# Power.net
KiCad netlist of a schematic drawn in Altium Designer
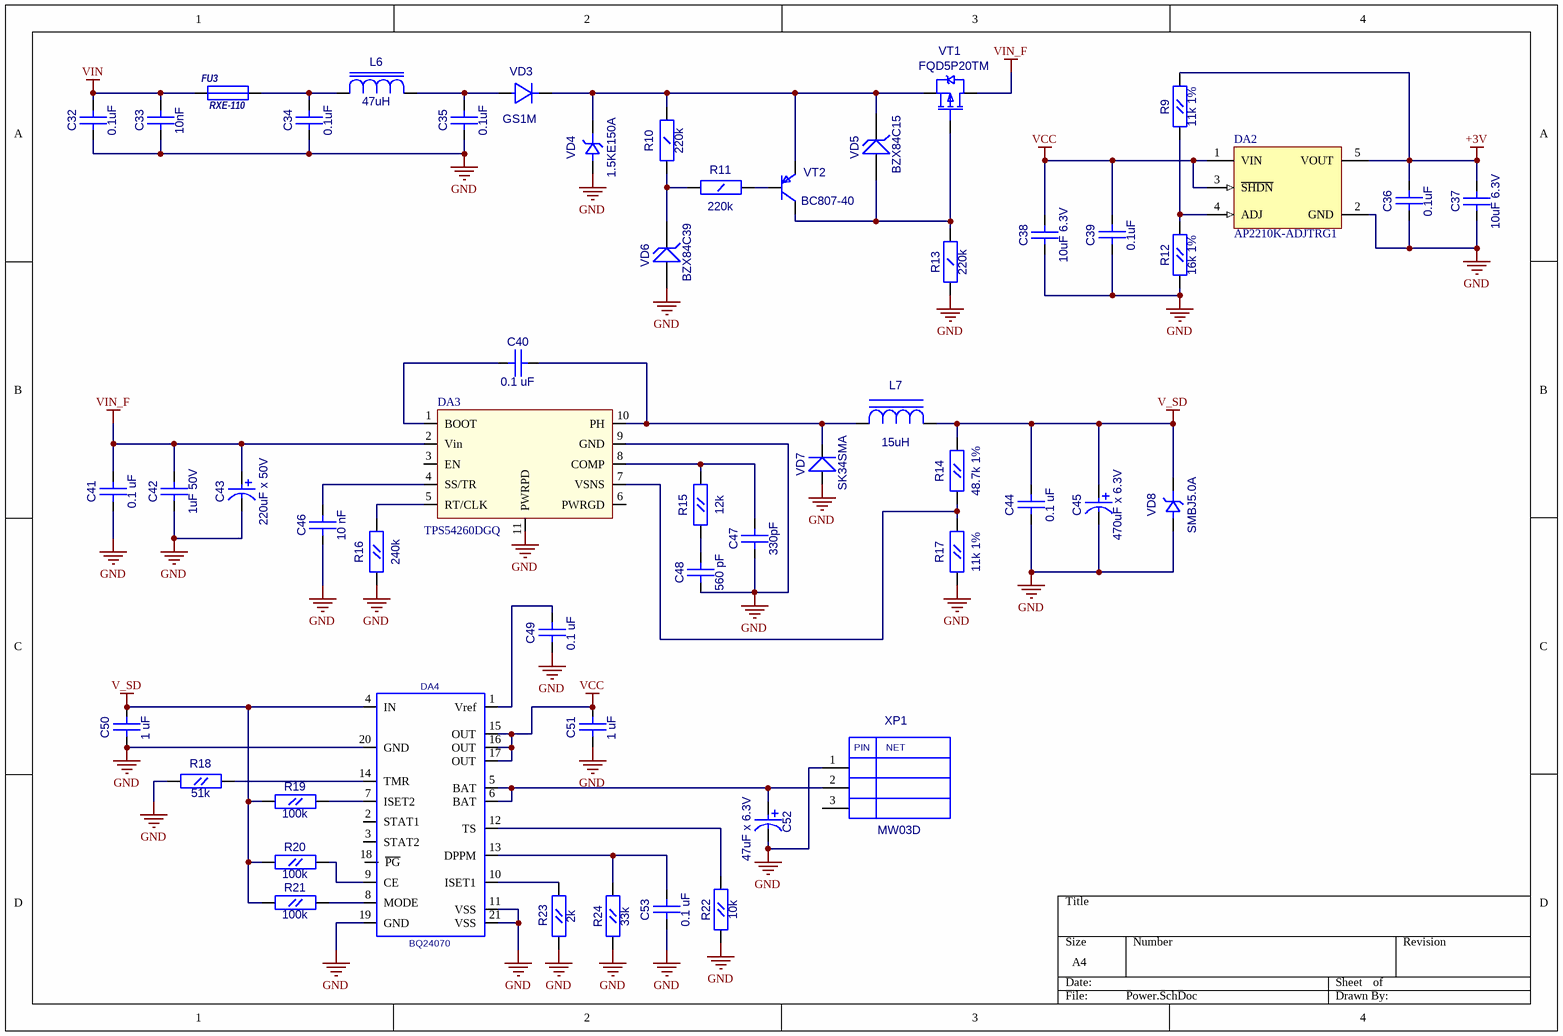
[diagram p0: Power.SchDoc]

(export (version "E")
  (design (tool "Eeschema 10.0.6"))
  (components
    (comp (ref "C32")
      (value "0.1uF")
      (footprint "CC1206")
      (description "CC1206")
      (libsource (lib "gprs_modem_2") (part "CC1206"))
    )
    (comp (ref "C33")
      (value "10nF")
      (footprint "CC1206")
      (description "CC1206")
      (libsource (lib "gprs_modem_2") (part "CC1206"))
    )
    (comp (ref "C34")
      (value "0.1uF")
      (footprint "CC1206")
      (description "CC1206")
      (libsource (lib "gprs_modem_2") (part "CC1206"))
    )
    (comp (ref "C35")
      (value "0.1uF")
      (footprint "CC1206")
      (description "CC1206")
      (libsource (lib "gprs_modem_2") (part "CC1206"))
    )
    (comp (ref "C36")
      (value "0.1uF")
      (footprint "CC0603")
      (description "CC0603")
      (libsource (lib "gprs_modem_2") (part "CC0603"))
    )
    (comp (ref "C37")
      (value "10uF 6.3V")
      (footprint "CC0805")
      (description "CC0805")
      (libsource (lib "gprs_modem_2") (part "CC0805"))
    )
    (comp (ref "C38")
      (value "10uF 6.3V")
      (footprint "CC0805")
      (description "CC0805")
      (libsource (lib "gprs_modem_2") (part "CC0805"))
    )
    (comp (ref "C39")
      (value "0.1uF")
      (footprint "CC0603")
      (description "CC0603")
      (libsource (lib "gprs_modem_2") (part "CC0603"))
    )
    (comp (ref "C40")
      (value "0.1 uF")
      (footprint "CC0603")
      (description "CC0603")
      (libsource (lib "gprs_modem_2") (part "CC0603"))
    )
    (comp (ref "C41")
      (value "0.1 uF")
      (footprint "CC0603")
      (description "CC0603")
      (libsource (lib "gprs_modem_2") (part "CC0603"))
    )
    (comp (ref "C42")
      (value "1uF 50V")
      (footprint "CC1206")
      (description "CC1206")
      (libsource (lib "gprs_modem_2") (part "CC1206"))
    )
    (comp (ref "C43")
      (value "220uF x 50V")
      (footprint "CC16X10_CAP0.5(1)(Primary)")
      (description "CAP0.5(1)")
      (libsource (lib "gprs_modem") (part "CAP0.5(1)"))
    )
    (comp (ref "C44")
      (value "0.1 uF")
      (footprint "CC0603")
      (description "CC0603")
      (libsource (lib "*") (part "CC0603"))
    )
    (comp (ref "C45")
      (value "470uF x 6.3V")
      (footprint "TAJ-D-1M")
      (description "TAJ-D")
      (libsource (lib "gprs_modem") (part "TAJ-D"))
    )
    (comp (ref "C46")
      (value "10 nF")
      (footprint "CC0603")
      (description "CC0603")
      (libsource (lib "gprs_modem_2") (part "CC0603"))
    )
    (comp (ref "C47")
      (value "330pF")
      (footprint "CC0603")
      (description "CC0603")
      (libsource (lib "gprs_modem_2") (part "CC0603"))
    )
    (comp (ref "C48")
      (value "560 pF")
      (footprint "CC0603")
      (description "CC0603")
      (libsource (lib "gprs_modem_2") (part "CC0603"))
    )
    (comp (ref "C49")
      (value "0.1 uF")
      (footprint "CC0603")
      (description "CC0603")
      (libsource (lib "gprs_modem_2") (part "CC0603"))
    )
    (comp (ref "C50")
      (value "1 uF")
      (footprint "CC0603")
      (description "CC0603")
      (libsource (lib "gprs_modem_2") (part "CC0603"))
    )
    (comp (ref "C51")
      (value "1 uF")
      (footprint "CC0603")
      (description "CC0603")
      (libsource (lib "*") (part "CC0603"))
    )
    (comp (ref "C52")
      (value "47uF x 6.3V")
      (footprint "TAJ-A_M")
      (description "TAJ-A")
      (libsource (lib "gprs_modem_2") (part "TAJ-A"))
    )
    (comp (ref "C53")
      (value "0.1 uF")
      (footprint "CC0603")
      (description "CC0603")
      (libsource (lib "gprs_modem_2") (part "CC0603"))
    )
    (comp (ref "DA2")
      (value "AP2210K-ADJTRG1")
      (footprint "SOT23-5")
      (fields (field (name "PUBLISHER") "Altium Limited"))
      (libsource (lib "gprs_modem_2") (part "MCP1824T-ADJE/OT"))
    )
    (comp (ref "DA3")
      (value "TPS54260DGQ")
      (footprint "S-PDSO-G10")
      (libsource (lib "gprs_modem") (part "TPS54260DGQ"))
    )
    (comp (ref "DA4")
      (value "BQ24070")
      (footprint "P-PQFP-N20")
      (libsource (lib "gprs_modem") (part "BQ24070"))
    )
    (comp (ref "FU3") (value "RXE-110") (footprint "RXE-110") (libsource (lib "gprs_modem") (part "RXE-110")))
    (comp (ref "L6")
      (value "47uH")
      (footprint "SDR0603")
      (description "SDR0603")
      (libsource (lib "gprs_modem_2") (part "SDR0603"))
    )
    (comp (ref "L7")
      (value "15uH")
      (footprint "SDR0805")
      (description "SDR0805")
      (libsource (lib "gprs_modem") (part "SDR0805"))
    )
    (comp (ref "R9")
      (value "11k 1%")
      (footprint "RC0603")
      (description "RC0603")
      (libsource (lib "gprs_modem_2") (part "RC0603"))
    )
    (comp (ref "R10")
      (value "220k")
      (footprint "RC1206")
      (description "RC1206")
      (libsource (lib "gprs_modem_2") (part "RC1206"))
    )
    (comp (ref "R11")
      (value "220k")
      (footprint "RC1206")
      (description "RC1206")
      (libsource (lib "gprs_modem_2") (part "RC1206"))
    )
    (comp (ref "R12")
      (value "16k 1%")
      (footprint "RC0603")
      (description "RC0603")
      (libsource (lib "gprs_modem_2") (part "RC0603"))
    )
    (comp (ref "R13")
      (value "220k")
      (footprint "RC1206")
      (description "RC1206")
      (libsource (lib "gprs_modem_2") (part "RC1206"))
    )
    (comp (ref "R14")
      (value "48.7k 1%")
      (footprint "RC0603")
      (description "RC0603")
      (libsource (lib "gprs_modem_2") (part "RC0603"))
    )
    (comp (ref "R15")
      (value "12k")
      (footprint "RC0603")
      (description "RC0603")
      (libsource (lib "gprs_modem_2") (part "RC0603"))
    )
    (comp (ref "R16")
      (value "240k")
      (footprint "RC0603")
      (description "RC0603")
      (libsource (lib "gprs_modem_2") (part "RC0603"))
    )
    (comp (ref "R17")
      (value "11k 1%")
      (footprint "RC0603")
      (description "RC0603")
      (libsource (lib "gprs_modem_2") (part "RC0603"))
    )
    (comp (ref "R18")
      (value "51k")
      (footprint "RC0603")
      (description "RC0603")
      (libsource (lib "gprs_modem_2") (part "RC0603"))
    )
    (comp (ref "R19")
      (value "100k")
      (footprint "RC0603")
      (description "RC0603")
      (libsource (lib "gprs_modem_2") (part "RC0603"))
    )
    (comp (ref "R20")
      (value "100k")
      (footprint "RC0603")
      (description "RC0603")
      (libsource (lib "gprs_modem_2") (part "RC0603"))
    )
    (comp (ref "R21")
      (value "100k")
      (footprint "RC0603")
      (description "RC0603")
      (libsource (lib "*") (part "RC0603"))
    )
    (comp (ref "R22")
      (value "10k")
      (footprint "RC0603")
      (description "RC0603")
      (libsource (lib "*") (part "RC0603"))
    )
    (comp (ref "R23")
      (value "2k")
      (footprint "RC0603")
      (description "RC0603")
      (libsource (lib "*") (part "RC0603"))
    )
    (comp (ref "R24")
      (value "33k")
      (footprint "RC0603")
      (description "RC0603")
      (libsource (lib "*") (part "RC0603"))
    )
    (comp (ref "VD3") (value "GS1M") (footprint "SMA") (libsource (lib "gprs_modem") (part "GS1M")))
    (comp (ref "VD4")
      (value "1.5KE150A")
      (footprint "DO-201")
      (description "1.5KE")
      (libsource (lib "gprs_modem") (part "1.5KE"))
    )
    (comp (ref "VD5")
      (value "BZX84C15")
      (footprint "SOT-23(123)")
      (description "Zener Voltage Regulator Diode")
      (libsource (lib "gprs_modem_2") (part "BZX84"))
    )
    (comp (ref "VD6")
      (value "BZX84C39")
      (footprint "SOT-23(123)")
      (description "Zener Voltage Regulator Diode")
      (libsource (lib "gprs_modem_2") (part "BZX84"))
    )
    (comp (ref "VD7")
      (value "SK34SMA")
      (footprint "SMA")
      (description "Schottky Rectifier")
      (libsource (lib "gprs_modem") (part "SK34SMA"))
    )
    (comp (ref "VD8")
      (value "SMBJ5.0A")
      (footprint "SMB")
      (description "SMBJ")
      (libsource (lib "gprs_modem") (part "SMBJ"))
    )
    (comp (ref "VT1")
      (value "FQD5P20TM")
      (footprint "D-PAK(TO-252AA)")
      (description "HEXFET Power MOSFET")
      (libsource (lib "gprs_modem_2") (part "IRFR9220"))
    )
    (comp (ref "VT2")
      (value "BC807-40")
      (footprint "SOT-23(123)")
      (description "BC857B")
      (libsource (lib "gprs_modem") (part "BC857B"))
    )
    (comp (ref "XP1") (value "MW03D") (footprint "MW03D") (libsource (lib "gprs_modem") (part "MW03D")))
  )
  (nets
    (net (code "1") (name "+3V") (class "Default")
      (node (ref "C36") (pin "1") (pinfunction "A_1") (pintype "passive"))
      (node (ref "C37") (pin "2") (pinfunction "B_2") (pintype "passive"))
      (node (ref "DA2") (pin "5") (pinfunction "VOUT_5") (pintype "power_in"))
      (node (ref "R9") (pin "2") (pinfunction "B_2") (pintype "passive"))
    )
    (net (code "2") (name "GND") (class "Default")
      (node (ref "C32") (pin "1") (pinfunction "A_1") (pintype "passive"))
      (node (ref "C33") (pin "1") (pinfunction "A_1") (pintype "passive"))
      (node (ref "C34") (pin "1") (pinfunction "A_1") (pintype "passive"))
      (node (ref "C35") (pin "1") (pinfunction "A_1") (pintype "passive"))
      (node (ref "C36") (pin "2") (pinfunction "B_2") (pintype "passive"))
      (node (ref "C37") (pin "1") (pinfunction "A_1") (pintype "passive"))
      (node (ref "C38") (pin "1") (pinfunction "A_1") (pintype "passive"))
      (node (ref "C39") (pin "2") (pinfunction "B_2") (pintype "passive"))
      (node (ref "C41") (pin "1") (pinfunction "A_1") (pintype "passive"))
      (node (ref "C42") (pin "1") (pinfunction "A_1") (pintype "passive"))
      (node (ref "C43") (pin "1") (pintype "passive"))
      (node (ref "C44") (pin "2") (pinfunction "B_2") (pintype "passive"))
      (node (ref "C45") (pin "2") (pinfunction "B_2") (pintype "passive"))
      (node (ref "C46") (pin "1") (pinfunction "A_1") (pintype "passive"))
      (node (ref "C47") (pin "1") (pinfunction "A_1") (pintype "passive"))
      (node (ref "C48") (pin "1") (pinfunction "A_1") (pintype "passive"))
      (node (ref "C49") (pin "2") (pinfunction "B_2") (pintype "passive"))
      (node (ref "C50") (pin "2") (pinfunction "B_2") (pintype "passive"))
      (node (ref "C51") (pin "2") (pinfunction "B_2") (pintype "passive"))
      (node (ref "C52") (pin "2") (pinfunction "B_2") (pintype "passive"))
      (node (ref "C53") (pin "2") (pinfunction "B_2") (pintype "passive"))
      (node (ref "DA2") (pin "2") (pinfunction "GND_2") (pintype "power_in"))
      (node (ref "DA3") (pin "11") (pinfunction "PWRPD_11") (pintype "passive"))
      (node (ref "DA3") (pin "9") (pinfunction "GND_9") (pintype "passive"))
      (node (ref "DA4") (pin "11") (pinfunction "VSS_11") (pintype "passive"))
      (node (ref "DA4") (pin "19") (pinfunction "GND_19") (pintype "passive"))
      (node (ref "DA4") (pin "20") (pinfunction "GND_20") (pintype "passive"))
      (node (ref "DA4") (pin "21") (pinfunction "VSS_21") (pintype "passive"))
      (node (ref "R12") (pin "1") (pinfunction "A_1") (pintype "passive"))
      (node (ref "R13") (pin "2") (pinfunction "B_2") (pintype "passive"))
      (node (ref "R16") (pin "1") (pinfunction "A_1") (pintype "passive"))
      (node (ref "R17") (pin "1") (pinfunction "A_1") (pintype "passive"))
      (node (ref "R18") (pin "1") (pinfunction "A_1") (pintype "passive"))
      (node (ref "R22") (pin "1") (pinfunction "A_1") (pintype "passive"))
      (node (ref "R23") (pin "1") (pinfunction "A_1") (pintype "passive"))
      (node (ref "R24") (pin "1") (pinfunction "A_1") (pintype "passive"))
      (node (ref "VD4") (pin "1") (pinfunction "A_1") (pintype "passive"))
      (node (ref "VD6") (pin "1") (pinfunction "A_1") (pintype "passive"))
      (node (ref "VD7") (pin "1") (pinfunction "A_1") (pintype "passive"))
      (node (ref "VD8") (pin "1") (pinfunction "A_1") (pintype "passive"))
      (node (ref "XP1") (pin "1") (pinfunction "1_1") (pintype "passive"))
    )
    (net (code "3") (name "Net-(C34-B)") (class "Default")
      (node (ref "C34") (pin "2") (pinfunction "B_2") (pintype "passive"))
      (node (ref "FU3") (pin "2") (pintype "passive"))
      (node (ref "L6") (pin "1") (pintype "passive"))
    )
    (net (code "4") (name "Net-(C35-B)") (class "Default")
      (node (ref "C35") (pin "2") (pinfunction "B_2") (pintype "passive"))
      (node (ref "L6") (pin "2") (pintype "passive"))
      (node (ref "VD3") (pin "1") (pinfunction "A_1") (pintype "passive"))
    )
    (net (code "5") (name "Net-(C40-A)") (class "Default")
      (node (ref "C40") (pin "1") (pinfunction "A_1") (pintype "passive"))
      (node (ref "DA3") (pin "1") (pinfunction "BOOT_1") (pintype "passive"))
    )
    (net (code "6") (name "Net-(C40-B)") (class "Default")
      (node (ref "C40") (pin "2") (pinfunction "B_2") (pintype "passive"))
      (node (ref "DA3") (pin "10") (pinfunction "PH_10") (pintype "passive"))
      (node (ref "L7") (pin "1") (pinfunction "C_1") (pintype "passive"))
      (node (ref "VD7") (pin "2") (pinfunction "K_2") (pintype "passive"))
    )
    (net (code "7") (name "Net-(C46-B)") (class "Default")
      (node (ref "C46") (pin "2") (pinfunction "B_2") (pintype "passive"))
      (node (ref "DA3") (pin "4") (pinfunction "SS/TR_4") (pintype "passive"))
    )
    (net (code "8") (name "Net-(C47-B)") (class "Default")
      (node (ref "C47") (pin "2") (pinfunction "B_2") (pintype "passive"))
      (node (ref "DA3") (pin "8") (pinfunction "COMP_8") (pintype "passive"))
      (node (ref "R15") (pin "2") (pinfunction "B_2") (pintype "passive"))
    )
    (net (code "9") (name "Net-(C48-B)") (class "Default")
      (node (ref "C48") (pin "2") (pinfunction "B_2") (pintype "passive"))
      (node (ref "R15") (pin "1") (pinfunction "A_1") (pintype "passive"))
    )
    (net (code "10") (name "Net-(C49-A)") (class "Default")
      (node (ref "C49") (pin "1") (pinfunction "A_1") (pintype "passive"))
      (node (ref "DA4") (pin "1") (pinfunction "Vref_1") (pintype "passive"))
    )
    (net (code "11") (name "Net-(C52-A)") (class "Default")
      (node (ref "C52") (pin "1") (pinfunction "A_1") (pintype "passive"))
      (node (ref "DA4") (pin "5") (pinfunction "BAT_5") (pintype "passive"))
      (node (ref "DA4") (pin "6") (pinfunction "BAT_6") (pintype "passive"))
      (node (ref "XP1") (pin "2") (pinfunction "2_2") (pintype "passive"))
    )
    (net (code "12") (name "Net-(C53-A)") (class "Default")
      (node (ref "C53") (pin "1") (pinfunction "A_1") (pintype "passive"))
      (node (ref "DA4") (pin "13") (pinfunction "DPPM_13") (pintype "passive"))
      (node (ref "R24") (pin "2") (pinfunction "B_2") (pintype "passive"))
    )
    (net (code "13") (name "Net-(DA2-ADJ)") (class "Default")
      (node (ref "DA2") (pin "4") (pinfunction "ADJ_4") (pintype "input"))
      (node (ref "R12") (pin "2") (pinfunction "B_2") (pintype "passive"))
      (node (ref "R9") (pin "1") (pinfunction "A_1") (pintype "passive"))
    )
    (net (code "14") (name "Net-(DA3-RT{slash}CLK)") (class "Default")
      (node (ref "DA3") (pin "5") (pinfunction "RT/CLK_5") (pintype "passive"))
      (node (ref "R16") (pin "2") (pinfunction "B_2") (pintype "passive"))
    )
    (net (code "15") (name "Net-(DA3-VSNS)") (class "Default")
      (node (ref "DA3") (pin "7") (pinfunction "VSNS_7") (pintype "passive"))
      (node (ref "R14") (pin "1") (pinfunction "A_1") (pintype "passive"))
      (node (ref "R17") (pin "2") (pinfunction "B_2") (pintype "passive"))
    )
    (net (code "16") (name "Net-(DA4-CE)") (class "Default")
      (node (ref "DA4") (pin "9") (pinfunction "CE_9") (pintype "passive"))
      (node (ref "R20") (pin "2") (pinfunction "B_2") (pintype "passive"))
    )
    (net (code "17") (name "Net-(DA4-ISET1)") (class "Default")
      (node (ref "DA4") (pin "10") (pinfunction "ISET1_10") (pintype "passive"))
      (node (ref "R23") (pin "2") (pinfunction "B_2") (pintype "passive"))
    )
    (net (code "18") (name "Net-(DA4-ISET2)") (class "Default")
      (node (ref "DA4") (pin "7") (pinfunction "ISET2_7") (pintype "passive"))
      (node (ref "R19") (pin "2") (pinfunction "B_2") (pintype "passive"))
    )
    (net (code "19") (name "Net-(DA4-MODE)") (class "Default")
      (node (ref "DA4") (pin "8") (pinfunction "MODE_8") (pintype "passive"))
      (node (ref "R21") (pin "2") (pinfunction "B_2") (pintype "passive"))
    )
    (net (code "20") (name "Net-(DA4-TMR)") (class "Default")
      (node (ref "DA4") (pin "14") (pinfunction "TMR_14") (pintype "passive"))
      (node (ref "R18") (pin "2") (pinfunction "B_2") (pintype "passive"))
    )
    (net (code "21") (name "Net-(DA4-TS)") (class "Default")
      (node (ref "DA4") (pin "12") (pinfunction "TS_12") (pintype "passive"))
      (node (ref "R22") (pin "2") (pinfunction "B_2") (pintype "passive"))
    )
    (net (code "22") (name "Net-(R10-A)") (class "Default")
      (node (ref "R10") (pin "1") (pinfunction "A_1") (pintype "passive"))
      (node (ref "R11") (pin "1") (pinfunction "A_1") (pintype "passive"))
      (node (ref "VD6") (pin "3") (pinfunction "K_3") (pintype "passive"))
    )
    (net (code "23") (name "Net-(R10-B)") (class "Default")
      (node (ref "R10") (pin "2") (pinfunction "B_2") (pintype "passive"))
      (node (ref "VD3") (pin "2") (pinfunction "K_2") (pintype "passive"))
      (node (ref "VD4") (pin "2") (pinfunction "K_2") (pintype "passive"))
      (node (ref "VD5") (pin "3") (pinfunction "K_3") (pintype "passive"))
      (node (ref "VT1") (pin "2") (pinfunction "S_2") (pintype "passive"))
      (node (ref "VT2") (pin "2") (pinfunction "E_2") (pintype "passive"))
    )
    (net (code "24") (name "Net-(R11-B)") (class "Default")
      (node (ref "R11") (pin "2") (pinfunction "B_2") (pintype "passive"))
      (node (ref "VT2") (pin "1") (pinfunction "B_1") (pintype "passive"))
    )
    (net (code "25") (name "Net-(R13-A)") (class "Default")
      (node (ref "R13") (pin "1") (pinfunction "A_1") (pintype "passive"))
      (node (ref "VD5") (pin "1") (pinfunction "A_1") (pintype "passive"))
      (node (ref "VT1") (pin "1") (pinfunction "G_1") (pintype "passive"))
      (node (ref "VT2") (pin "3") (pinfunction "C_3") (pintype "passive"))
    )
    (net (code "26") (name "VCC") (class "Default")
      (node (ref "C38") (pin "2") (pinfunction "B_2") (pintype "passive"))
      (node (ref "C39") (pin "1") (pinfunction "A_1") (pintype "passive"))
      (node (ref "C51") (pin "1") (pinfunction "A_1") (pintype "passive"))
      (node (ref "DA2") (pin "1") (pinfunction "VIN_1") (pintype "power_in"))
      (node (ref "DA2") (pin "3") (pinfunction "~{SHDN}_3") (pintype "input"))
      (node (ref "DA4") (pin "15") (pinfunction "OUT_15") (pintype "passive"))
      (node (ref "DA4") (pin "16") (pinfunction "OUT_16") (pintype "passive"))
      (node (ref "DA4") (pin "17") (pinfunction "OUT_17") (pintype "passive"))
    )
    (net (code "27") (name "VIN") (class "Default")
      (node (ref "C32") (pin "2") (pinfunction "B_2") (pintype "passive"))
      (node (ref "C33") (pin "2") (pinfunction "B_2") (pintype "passive"))
      (node (ref "FU3") (pin "1") (pintype "passive"))
    )
    (net (code "28") (name "VIN_F") (class "Default")
      (node (ref "C41") (pin "2") (pinfunction "B_2") (pintype "passive"))
      (node (ref "C42") (pin "2") (pinfunction "B_2") (pintype "passive"))
      (node (ref "C43") (pin "2") (pintype "passive"))
      (node (ref "DA3") (pin "2") (pinfunction "Vin_2") (pintype "passive"))
      (node (ref "VT1") (pin "3") (pinfunction "D_3") (pintype "passive"))
    )
    (net (code "29") (name "V_SD") (class "Default")
      (node (ref "C44") (pin "1") (pinfunction "A_1") (pintype "passive"))
      (node (ref "C45") (pin "1") (pinfunction "A_1") (pintype "passive"))
      (node (ref "C50") (pin "1") (pinfunction "A_1") (pintype "passive"))
      (node (ref "DA4") (pin "4") (pinfunction "IN_4") (pintype "passive"))
      (node (ref "L7") (pin "2") (pinfunction "A_2") (pintype "passive"))
      (node (ref "R14") (pin "2") (pinfunction "B_2") (pintype "passive"))
      (node (ref "R19") (pin "1") (pinfunction "A_1") (pintype "passive"))
      (node (ref "R20") (pin "1") (pinfunction "A_1") (pintype "passive"))
      (node (ref "R21") (pin "1") (pinfunction "A_1") (pintype "passive"))
      (node (ref "VD8") (pin "2") (pinfunction "K_2") (pintype "passive"))
    )
    (net (code "30") (name "unconnected-(DA3-EN-Pad3)") (class "Default")
      (node (ref "DA3") (pin "3") (pinfunction "EN_3") (pintype "passive"))
    )
    (net (code "31") (name "unconnected-(DA3-PWRGD-Pad6)") (class "Default")
      (node (ref "DA3") (pin "6") (pinfunction "PWRGD_6") (pintype "passive"))
    )
    (net (code "32") (name "unconnected-(DA4-STAT1-Pad2)") (class "Default")
      (node (ref "DA4") (pin "2") (pinfunction "STAT1_2") (pintype "passive"))
    )
    (net (code "33") (name "unconnected-(DA4-STAT2-Pad3)") (class "Default")
      (node (ref "DA4") (pin "3") (pinfunction "STAT2_3") (pintype "passive"))
    )
    (net (code "34") (name "unconnected-(DA4-~{PG}-Pad18)") (class "Default")
      (node (ref "DA4") (pin "18") (pinfunction "~{PG}_18") (pintype "passive"))
    )
    (net (code "35") (name "unconnected-(XP1-Pad3)") (class "Default")
      (node (ref "XP1") (pin "3") (pinfunction "3_3") (pintype "passive"))
    )
  )
)
